# Sheet1.net
KiCad netlist of a schematic drawn in Altium Designer
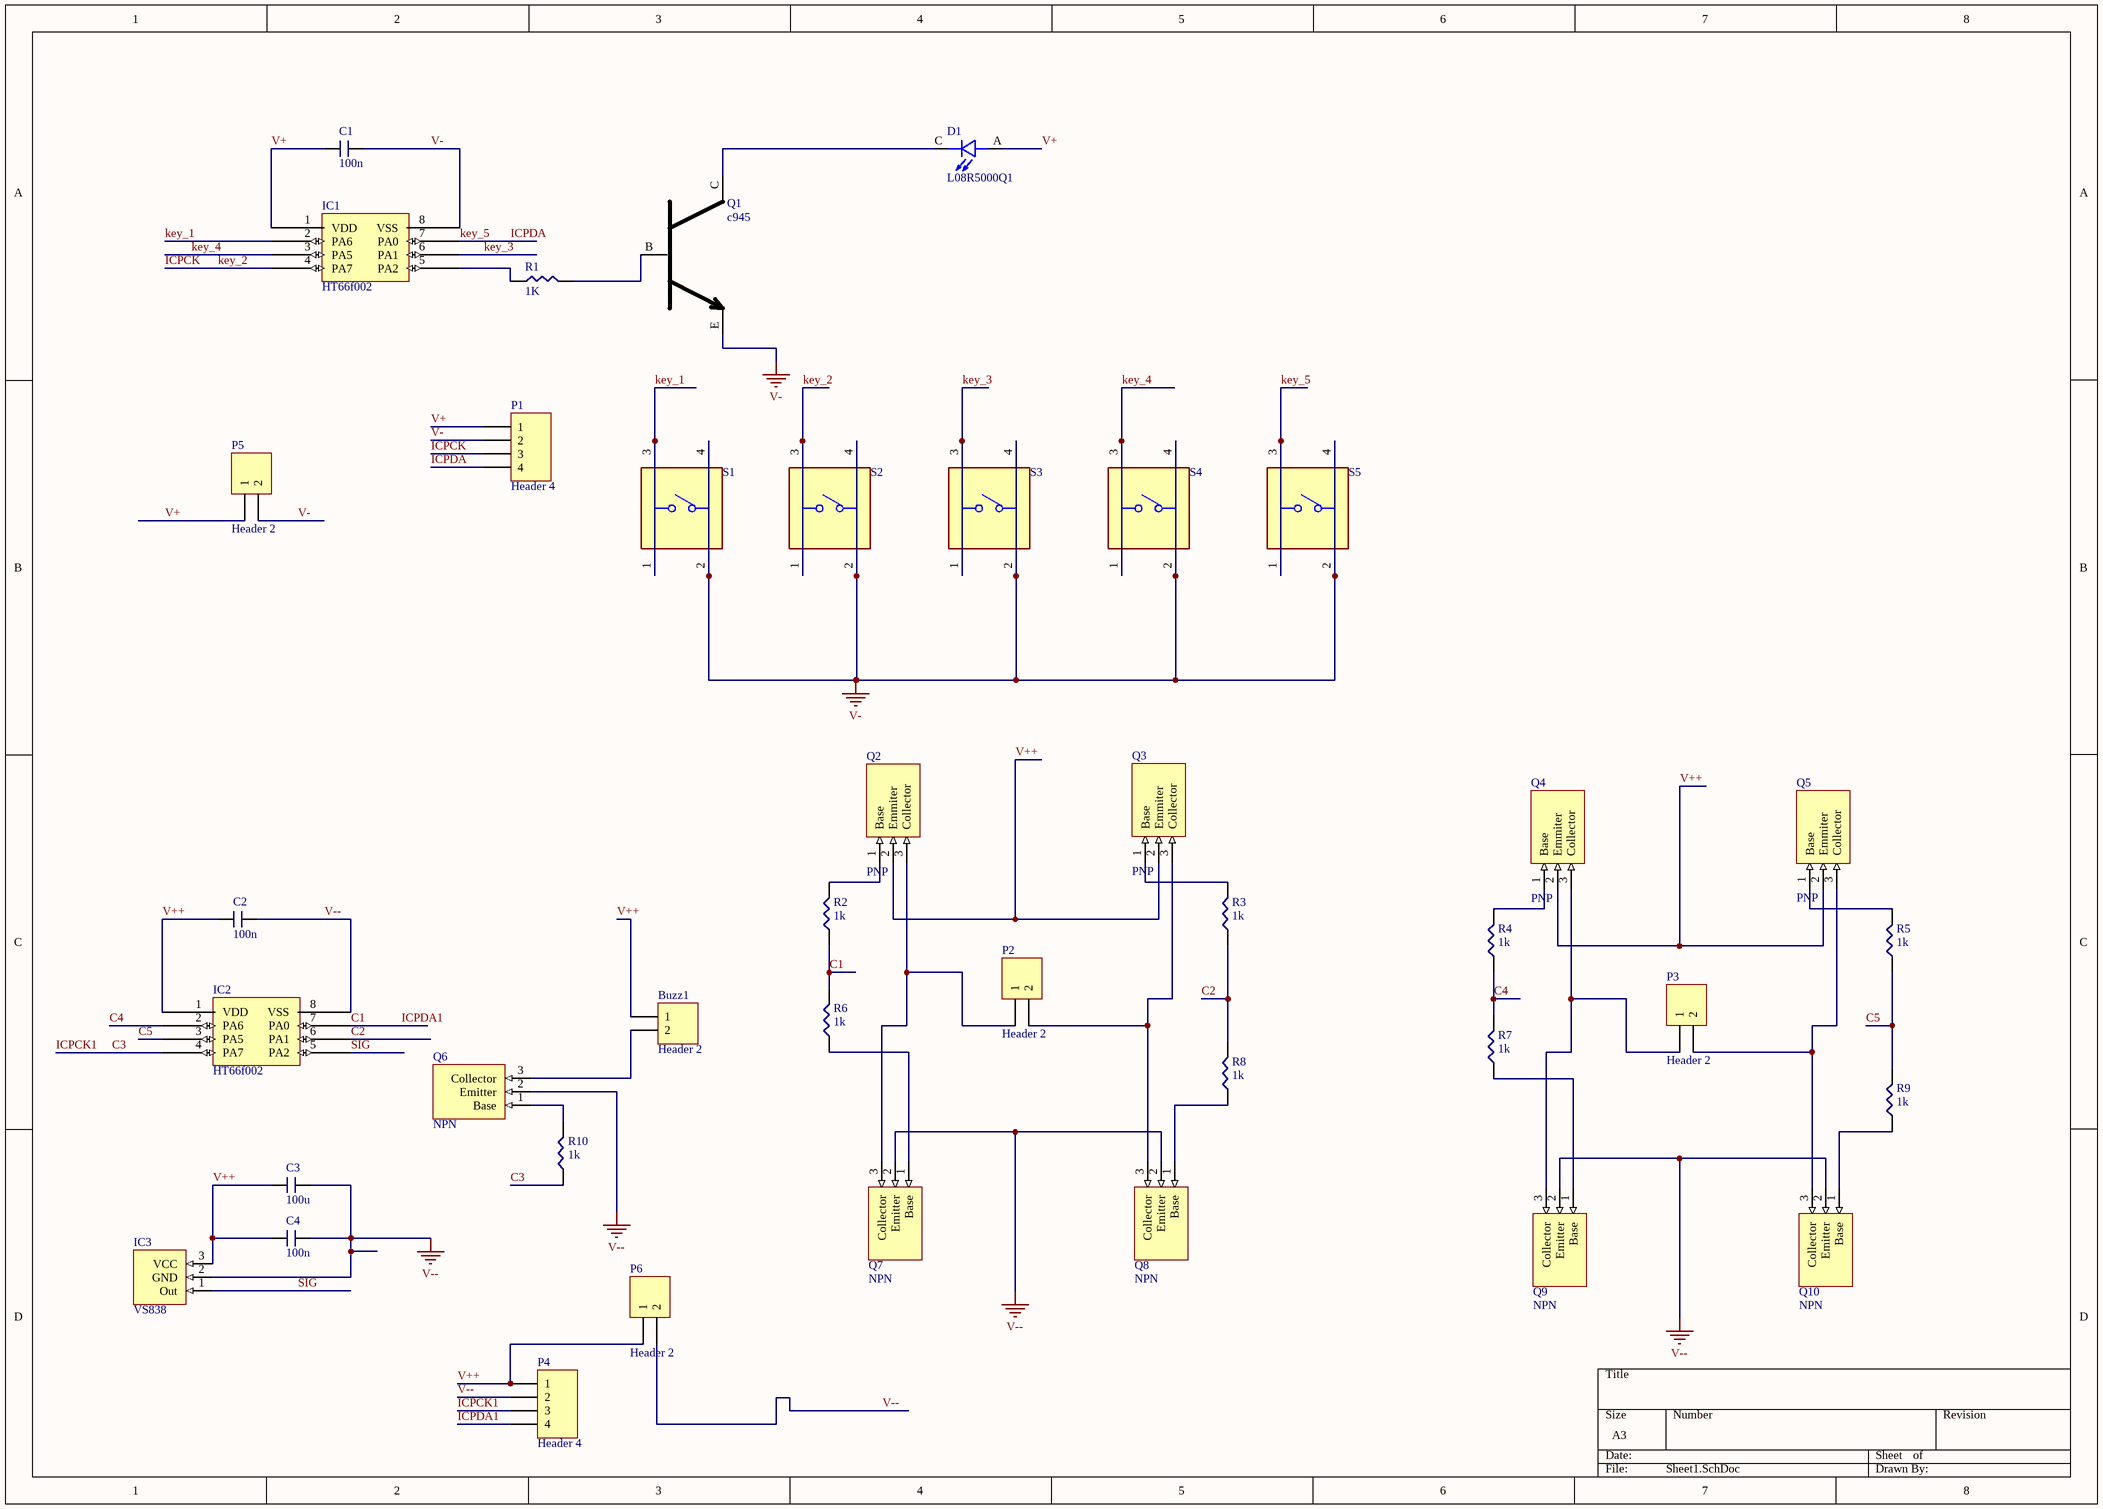
[diagram p0: Sheet1.SchDoc]

(export (version "E")
  (design (tool "Eeschema 10.0.6"))
  (components
    (comp (ref "Buzz1")
      (value "Header 2")
      (footprint "HDR1X2")
      (description "Header, 2-Pin")
      (fields (field (name "PUBLISHER") "Altium Limited"))
      (libsource (lib "") (part "Header 2_1"))
    )
    (comp (ref "C1")
      (value "100n")
      (footprint "CAPC2012X08N-805")
      (description "Standard Bipolar Capasitor")
      (fields (field (name "Comment") "Capacitor"))
      (libsource (lib "Caspian_GPS") (part "Capacitor"))
    )
    (comp (ref "C2")
      (value "100n")
      (footprint "CAPC2012X08N-805")
      (description "Standard Bipolar Capasitor")
      (fields (field (name "Comment") "Capacitor"))
      (libsource (lib "Caspian_GPS") (part "Capacitor"))
    )
    (comp (ref "C3")
      (value "100u")
      (footprint "CAPC2012X08N-805")
      (description "Standard Bipolar Capasitor")
      (fields (field (name "Comment") "Capacitor"))
      (libsource (lib "Caspian_GPS") (part "Capacitor"))
    )
    (comp (ref "C4")
      (value "100n")
      (footprint "CAPC2012X08N-805")
      (description "Standard Bipolar Capasitor")
      (fields (field (name "Comment") "Capacitor"))
      (libsource (lib "Caspian_GPS") (part "Capacitor"))
    )
    (comp (ref "D1")
      (value "L08R5000Q1")
      (footprint "LEDRD254W57D500H1070")
      (description "LED, Orange, Through Hole, T-1 3/4 (5mm), 30 mA, 2.1 V, 635 nm")
      (libsource (lib "L08R5000Q1") (part "L08R5000Q1"))
    )
    (comp (ref "IC1") (value "HT66f002") (footprint "ht66f002") (libsource (lib "Schlib1") (part "HT66f002")))
    (comp (ref "IC2") (value "HT66f002") (footprint "ht66f002") (libsource (lib "Schlib1") (part "HT66f002")))
    (comp (ref "IC3") (value "VS838") (footprint "VS838") (libsource (lib "Schlib1") (part "VS838")))
    (comp (ref "P1")
      (value "Header 4")
      (footprint "HDR1X4")
      (description "Header, 4-Pin")
      (fields (field (name "PUBLISHER") "Altium Limited"))
      (libsource (lib "Miscellaneous Connectors") (part "Header 4"))
    )
    (comp (ref "P2")
      (value "Header 2")
      (footprint "HDR1X2")
      (description "Header, 2-Pin")
      (fields (field (name "PUBLISHER") "Altium Limited"))
      (libsource (lib "Miscellaneous Connectors") (part "Header 2"))
    )
    (comp (ref "P3")
      (value "Header 2")
      (footprint "HDR1X2")
      (description "Header, 2-Pin")
      (fields (field (name "PUBLISHER") "Altium Limited"))
      (libsource (lib "Miscellaneous Connectors") (part "Header 2"))
    )
    (comp (ref "P4")
      (value "Header 4")
      (footprint "HDR1X4")
      (description "Header, 4-Pin")
      (fields (field (name "PUBLISHER") "Altium Limited"))
      (libsource (lib "Miscellaneous Connectors") (part "Header 4"))
    )
    (comp (ref "P5")
      (value "Header 2")
      (footprint "HDR1X2")
      (description "Header, 2-Pin")
      (fields (field (name "PUBLISHER") "Altium Limited"))
      (libsource (lib "Miscellaneous Connectors") (part "Header 2"))
    )
    (comp (ref "P6")
      (value "Header 2")
      (footprint "HDR1X2")
      (description "Header, 2-Pin")
      (fields (field (name "PUBLISHER") "Altium Limited"))
      (libsource (lib "Miscellaneous Connectors") (part "Header 2"))
    )
    (comp (ref "Q1") (value "c945") (footprint "c945") (libsource (lib "my_lib") (part "c945")))
    (comp (ref "Q2") (value "PNP") (footprint "pmbt8550") (libsource (lib "Schlib1") (part "pmbt8550")))
    (comp (ref "Q3") (value "PNP") (footprint "pmbt8550") (libsource (lib "Schlib1") (part "pmbt8550")))
    (comp (ref "Q4") (value "PNP") (footprint "pmbt8550") (libsource (lib "Schlib1") (part "pmbt8550")))
    (comp (ref "Q5") (value "PNP") (footprint "pmbt8550") (libsource (lib "Schlib1") (part "pmbt8550")))
    (comp (ref "Q6") (value "NPN") (footprint "MMBT8050") (libsource (lib "Schlib1") (part "MMBT8050")))
    (comp (ref "Q7") (value "NPN") (footprint "MMBT8050") (libsource (lib "") (part "MMBT8050_1")))
    (comp (ref "Q8") (value "NPN") (footprint "MMBT8050") (libsource (lib "") (part "MMBT8050_1")))
    (comp (ref "Q9") (value "NPN") (footprint "MMBT8050") (libsource (lib "") (part "MMBT8050_1")))
    (comp (ref "Q10") (value "NPN") (footprint "MMBT8050") (libsource (lib "") (part "MMBT8050_1")))
    (comp (ref "R1")
      (value "1K")
      (footprint "RESC2012X06N-805")
      (description "Standard Resistor")
      (fields (field (name "Comment") "Resistor"))
      (libsource (lib "Caspian_GPS") (part "Resistor"))
    )
    (comp (ref "R2")
      (value "1k")
      (footprint "RESC2012X06N-805")
      (description "Standard Resistor")
      (fields (field (name "Comment") "Resistor"))
      (libsource (lib "Caspian_GPS") (part "Resistor"))
    )
    (comp (ref "R3")
      (value "1k")
      (footprint "RESC2012X06N-805")
      (description "Standard Resistor")
      (fields (field (name "Comment") "Resistor"))
      (libsource (lib "Caspian_GPS") (part "Resistor"))
    )
    (comp (ref "R4")
      (value "1k")
      (footprint "RESC2012X06N-805")
      (description "Standard Resistor")
      (fields (field (name "Comment") "Resistor"))
      (libsource (lib "Caspian_GPS") (part "Resistor"))
    )
    (comp (ref "R5")
      (value "1k")
      (footprint "RESC2012X06N-805")
      (description "Standard Resistor")
      (fields (field (name "Comment") "Resistor"))
      (libsource (lib "Caspian_GPS") (part "Resistor"))
    )
    (comp (ref "R6")
      (value "1k")
      (footprint "RESC2012X06N-805")
      (description "Standard Resistor")
      (fields (field (name "Comment") "Resistor"))
      (libsource (lib "Caspian_GPS") (part "Resistor"))
    )
    (comp (ref "R7")
      (value "1k")
      (footprint "RESC2012X06N-805")
      (description "Standard Resistor")
      (fields (field (name "Comment") "Resistor"))
      (libsource (lib "Caspian_GPS") (part "Resistor"))
    )
    (comp (ref "R8")
      (value "1k")
      (footprint "RESC2012X06N-805")
      (description "Standard Resistor")
      (fields (field (name "Comment") "Resistor"))
      (libsource (lib "Caspian_GPS") (part "Resistor"))
    )
    (comp (ref "R9")
      (value "1k")
      (footprint "RESC2012X06N-805")
      (description "Standard Resistor")
      (fields (field (name "Comment") "Resistor"))
      (libsource (lib "Caspian_GPS") (part "Resistor"))
    )
    (comp (ref "R10")
      (value "1k")
      (footprint "RESC2012X06N-805")
      (description "Standard Resistor")
      (fields (field (name "Comment") "Resistor"))
      (libsource (lib "Caspian_GPS") (part "Resistor"))
    )
    (comp (ref "S1")
      (value "TS04-66-95-BK-100-SMT")
      (footprint "SW_TS04-66-95-BK-100-SMT")
      (description "6 x 6 mm, 4.3~9.5 mm Actuator Height, 100~260 gf, Surface Mount, SPST, Tactile Switch")
      (fields (field (name "MF") "CUI Devices"))
      (libsource (lib "TS04-66-95-BK-100-SMT") (part "TS04-66-95-BK-100-SMT"))
    )
    (comp (ref "S2")
      (value "TS04-66-95-BK-100-SMT")
      (footprint "SW_TS04-66-95-BK-100-SMT")
      (description "6 x 6 mm, 4.3~9.5 mm Actuator Height, 100~260 gf, Surface Mount, SPST, Tactile Switch")
      (fields (field (name "MF") "CUI Devices"))
      (libsource (lib "TS04-66-95-BK-100-SMT") (part "TS04-66-95-BK-100-SMT"))
    )
    (comp (ref "S3")
      (value "TS04-66-95-BK-100-SMT")
      (footprint "SW_TS04-66-95-BK-100-SMT")
      (description "6 x 6 mm, 4.3~9.5 mm Actuator Height, 100~260 gf, Surface Mount, SPST, Tactile Switch")
      (fields (field (name "MF") "CUI Devices"))
      (libsource (lib "TS04-66-95-BK-100-SMT") (part "TS04-66-95-BK-100-SMT"))
    )
    (comp (ref "S4")
      (value "TS04-66-95-BK-100-SMT")
      (footprint "SW_TS04-66-95-BK-100-SMT")
      (description "6 x 6 mm, 4.3~9.5 mm Actuator Height, 100~260 gf, Surface Mount, SPST, Tactile Switch")
      (fields (field (name "MF") "CUI Devices"))
      (libsource (lib "TS04-66-95-BK-100-SMT") (part "TS04-66-95-BK-100-SMT"))
    )
    (comp (ref "S5")
      (value "TS04-66-95-BK-100-SMT")
      (footprint "SW_TS04-66-95-BK-100-SMT")
      (description "6 x 6 mm, 4.3~9.5 mm Actuator Height, 100~260 gf, Surface Mount, SPST, Tactile Switch")
      (fields (field (name "MF") "CUI Devices"))
      (libsource (lib "TS04-66-95-BK-100-SMT") (part "TS04-66-95-BK-100-SMT"))
    )
  )
  (nets
    (net (code "1") (name "/C1") (class "Default")
      (node (ref "IC2") (pin "7") (pinfunction "PA0_7") (pintype "bidirectional"))
      (node (ref "P4") (pin "4") (pinfunction "4_4") (pintype "passive"))
      (node (ref "R2") (pin "1") (pintype "passive"))
      (node (ref "R6") (pin "2") (pintype "passive"))
    )
    (net (code "2") (name "/C2") (class "Default")
      (node (ref "IC2") (pin "6") (pinfunction "PA1_6") (pintype "bidirectional"))
      (node (ref "R3") (pin "1") (pintype "passive"))
      (node (ref "R8") (pin "2") (pintype "passive"))
    )
    (net (code "3") (name "/C3") (class "Default")
      (node (ref "IC2") (pin "4") (pinfunction "PA7_4") (pintype "bidirectional"))
      (node (ref "P4") (pin "3") (pinfunction "3_3") (pintype "passive"))
      (node (ref "R10") (pin "1") (pintype "passive"))
    )
    (net (code "4") (name "/C4") (class "Default")
      (node (ref "IC2") (pin "2") (pinfunction "PA6_2") (pintype "bidirectional"))
      (node (ref "R4") (pin "1") (pintype "passive"))
      (node (ref "R7") (pin "2") (pintype "passive"))
    )
    (net (code "5") (name "/C5") (class "Default")
      (node (ref "IC2") (pin "3") (pinfunction "PA5_3") (pintype "bidirectional"))
      (node (ref "R5") (pin "1") (pintype "passive"))
      (node (ref "R9") (pin "2") (pintype "passive"))
    )
    (net (code "6") (name "/ICPCK") (class "Default")
      (node (ref "IC1") (pin "4") (pinfunction "PA7_4") (pintype "bidirectional"))
      (node (ref "P1") (pin "3") (pinfunction "3_3") (pintype "passive"))
      (node (ref "S2") (pin "1") (pinfunction "1_1") (pintype "passive"))
      (node (ref "S2") (pin "3") (pinfunction "3_3") (pintype "passive"))
    )
    (net (code "7") (name "/ICPDA") (class "Default")
      (node (ref "IC1") (pin "7") (pinfunction "PA0_7") (pintype "bidirectional"))
      (node (ref "P1") (pin "4") (pinfunction "4_4") (pintype "passive"))
      (node (ref "S5") (pin "1") (pinfunction "1_1") (pintype "passive"))
      (node (ref "S5") (pin "3") (pinfunction "3_3") (pintype "passive"))
    )
    (net (code "8") (name "/SIG") (class "Default")
      (node (ref "IC2") (pin "5") (pinfunction "PA2_5") (pintype "bidirectional"))
      (node (ref "IC3") (pin "1") (pinfunction "Out_1") (pintype "input"))
    )
    (net (code "9") (name "/V+") (class "Default")
      (node (ref "C1") (pin "1") (pintype "passive"))
      (node (ref "D1") (pin "A") (pinfunction "A_A") (pintype "passive"))
      (node (ref "IC1") (pin "1") (pinfunction "VDD_1") (pintype "power_in"))
      (node (ref "P1") (pin "1") (pinfunction "1_1") (pintype "passive"))
      (node (ref "P5") (pin "1") (pinfunction "1_1") (pintype "passive"))
    )
    (net (code "10") (name "/V++") (class "Default")
      (node (ref "Buzz1") (pin "1") (pinfunction "1_1") (pintype "passive"))
      (node (ref "C2") (pin "1") (pintype "passive"))
      (node (ref "C3") (pin "1") (pintype "passive"))
      (node (ref "C4") (pin "1") (pintype "passive"))
      (node (ref "IC2") (pin "1") (pinfunction "VDD_1") (pintype "power_in"))
      (node (ref "IC3") (pin "3") (pinfunction "VCC_3") (pintype "input"))
      (node (ref "P4") (pin "1") (pinfunction "1_1") (pintype "passive"))
      (node (ref "P6") (pin "1") (pinfunction "1_1") (pintype "passive"))
      (node (ref "Q2") (pin "2") (pinfunction "Emmiter_2") (pintype "input"))
      (node (ref "Q3") (pin "2") (pinfunction "Emmiter_2") (pintype "input"))
      (node (ref "Q4") (pin "2") (pinfunction "Emmiter_2") (pintype "input"))
      (node (ref "Q5") (pin "2") (pinfunction "Emmiter_2") (pintype "input"))
    )
    (net (code "11") (name "/key_1") (class "Default")
      (node (ref "IC1") (pin "2") (pinfunction "PA6_2") (pintype "bidirectional"))
      (node (ref "S1") (pin "1") (pinfunction "1_1") (pintype "passive"))
      (node (ref "S1") (pin "3") (pinfunction "3_3") (pintype "passive"))
    )
    (net (code "12") (name "/key_3") (class "Default")
      (node (ref "IC1") (pin "6") (pinfunction "PA1_6") (pintype "bidirectional"))
      (node (ref "S3") (pin "1") (pinfunction "1_1") (pintype "passive"))
      (node (ref "S3") (pin "3") (pinfunction "3_3") (pintype "passive"))
    )
    (net (code "13") (name "/key_4") (class "Default")
      (node (ref "IC1") (pin "3") (pinfunction "PA5_3") (pintype "bidirectional"))
      (node (ref "S4") (pin "1") (pinfunction "1_1") (pintype "passive"))
      (node (ref "S4") (pin "3") (pinfunction "3_3") (pintype "passive"))
    )
    (net (code "14") (name "Net-(D1-PadC)") (class "Default")
      (node (ref "D1") (pin "C") (pinfunction "C_C") (pintype "passive"))
      (node (ref "Q1") (pin "C") (pinfunction "C_C") (pintype "passive"))
    )
    (net (code "15") (name "Net-(IC1-PA2)") (class "Default")
      (node (ref "IC1") (pin "5") (pinfunction "PA2_5") (pintype "bidirectional"))
      (node (ref "R1") (pin "1") (pintype "passive"))
    )
    (net (code "16") (name "Net-(Q1-PadB)") (class "Default")
      (node (ref "Q1") (pin "B") (pinfunction "B_B") (pintype "passive"))
      (node (ref "R1") (pin "2") (pintype "passive"))
    )
    (net (code "17") (name "Net-(Q2-Base)") (class "Default")
      (node (ref "Q2") (pin "1") (pinfunction "Base_1") (pintype "input"))
      (node (ref "R2") (pin "2") (pintype "passive"))
    )
    (net (code "18") (name "Net-(Q2-Collector)") (class "Default")
      (node (ref "P2") (pin "1") (pinfunction "1_1") (pintype "passive"))
      (node (ref "Q2") (pin "3") (pinfunction "Collector_3") (pintype "input"))
      (node (ref "Q7") (pin "3") (pinfunction "Collector_3") (pintype "input"))
    )
    (net (code "19") (name "Net-(Q3-Base)") (class "Default")
      (node (ref "Q3") (pin "1") (pinfunction "Base_1") (pintype "input"))
      (node (ref "R3") (pin "2") (pintype "passive"))
    )
    (net (code "20") (name "Net-(Q3-Collector)") (class "Default")
      (node (ref "P2") (pin "2") (pinfunction "2_2") (pintype "passive"))
      (node (ref "Q3") (pin "3") (pinfunction "Collector_3") (pintype "input"))
      (node (ref "Q8") (pin "3") (pinfunction "Collector_3") (pintype "input"))
    )
    (net (code "21") (name "Net-(Q4-Base)") (class "Default")
      (node (ref "Q4") (pin "1") (pinfunction "Base_1") (pintype "input"))
      (node (ref "R4") (pin "2") (pintype "passive"))
    )
    (net (code "22") (name "Net-(Q4-Collector)") (class "Default")
      (node (ref "P3") (pin "1") (pinfunction "1_1") (pintype "passive"))
      (node (ref "Q4") (pin "3") (pinfunction "Collector_3") (pintype "input"))
      (node (ref "Q9") (pin "3") (pinfunction "Collector_3") (pintype "input"))
    )
    (net (code "23") (name "Net-(Q5-Base)") (class "Default")
      (node (ref "Q5") (pin "1") (pinfunction "Base_1") (pintype "input"))
      (node (ref "R5") (pin "2") (pintype "passive"))
    )
    (net (code "24") (name "Net-(Q6-Base)") (class "Default")
      (node (ref "Q6") (pin "1") (pinfunction "Base_1") (pintype "input"))
      (node (ref "R10") (pin "2") (pintype "passive"))
    )
    (net (code "25") (name "Net-(Q6-Collector)") (class "Default")
      (node (ref "Buzz1") (pin "2") (pinfunction "2_2") (pintype "passive"))
      (node (ref "Q6") (pin "3") (pinfunction "Collector_3") (pintype "input"))
    )
    (net (code "26") (name "Net-(Q7-Base)") (class "Default")
      (node (ref "Q7") (pin "1") (pinfunction "Base_1") (pintype "input"))
      (node (ref "R6") (pin "1") (pintype "passive"))
    )
    (net (code "27") (name "Net-(Q8-Base)") (class "Default")
      (node (ref "Q8") (pin "1") (pinfunction "Base_1") (pintype "input"))
      (node (ref "R8") (pin "1") (pintype "passive"))
    )
    (net (code "28") (name "Net-(Q9-Base)") (class "Default")
      (node (ref "Q9") (pin "1") (pinfunction "Base_1") (pintype "input"))
      (node (ref "R7") (pin "1") (pintype "passive"))
    )
    (net (code "29") (name "Net-(Q10-Base)") (class "Default")
      (node (ref "Q10") (pin "1") (pinfunction "Base_1") (pintype "input"))
      (node (ref "R9") (pin "1") (pintype "passive"))
    )
    (net (code "30") (name "Net-(Q10-Collector)") (class "Default")
      (node (ref "P3") (pin "2") (pinfunction "2_2") (pintype "passive"))
      (node (ref "Q10") (pin "3") (pinfunction "Collector_3") (pintype "input"))
      (node (ref "Q5") (pin "3") (pinfunction "Collector_3") (pintype "input"))
    )
    (net (code "31") (name "V-") (class "Default")
      (node (ref "C1") (pin "2") (pintype "passive"))
      (node (ref "IC1") (pin "8") (pinfunction "VSS_8") (pintype "power_in"))
      (node (ref "P1") (pin "2") (pinfunction "2_2") (pintype "passive"))
      (node (ref "P5") (pin "2") (pinfunction "2_2") (pintype "passive"))
      (node (ref "Q1") (pin "E") (pinfunction "E_E") (pintype "passive"))
      (node (ref "S1") (pin "2") (pinfunction "2_2") (pintype "passive"))
      (node (ref "S1") (pin "4") (pinfunction "4_4") (pintype "passive"))
      (node (ref "S2") (pin "2") (pinfunction "2_2") (pintype "passive"))
      (node (ref "S2") (pin "4") (pinfunction "4_4") (pintype "passive"))
      (node (ref "S3") (pin "2") (pinfunction "2_2") (pintype "passive"))
      (node (ref "S3") (pin "4") (pinfunction "4_4") (pintype "passive"))
      (node (ref "S4") (pin "2") (pinfunction "2_2") (pintype "passive"))
      (node (ref "S4") (pin "4") (pinfunction "4_4") (pintype "passive"))
      (node (ref "S5") (pin "2") (pinfunction "2_2") (pintype "passive"))
      (node (ref "S5") (pin "4") (pinfunction "4_4") (pintype "passive"))
    )
    (net (code "32") (name "V--") (class "Default")
      (node (ref "C2") (pin "2") (pintype "passive"))
      (node (ref "C3") (pin "2") (pintype "passive"))
      (node (ref "C4") (pin "2") (pintype "passive"))
      (node (ref "IC2") (pin "8") (pinfunction "VSS_8") (pintype "power_in"))
      (node (ref "IC3") (pin "2") (pinfunction "GND_2") (pintype "input"))
      (node (ref "P4") (pin "2") (pinfunction "2_2") (pintype "passive"))
      (node (ref "P6") (pin "2") (pinfunction "2_2") (pintype "passive"))
      (node (ref "Q10") (pin "2") (pinfunction "Emitter_2") (pintype "input"))
      (node (ref "Q6") (pin "2") (pinfunction "Emitter_2") (pintype "input"))
      (node (ref "Q7") (pin "2") (pinfunction "Emitter_2") (pintype "input"))
      (node (ref "Q8") (pin "2") (pinfunction "Emitter_2") (pintype "input"))
      (node (ref "Q9") (pin "2") (pinfunction "Emitter_2") (pintype "input"))
    )
  )
)
